# Reader_0001.net
KiCad netlist of a schematic drawn in EAGLE
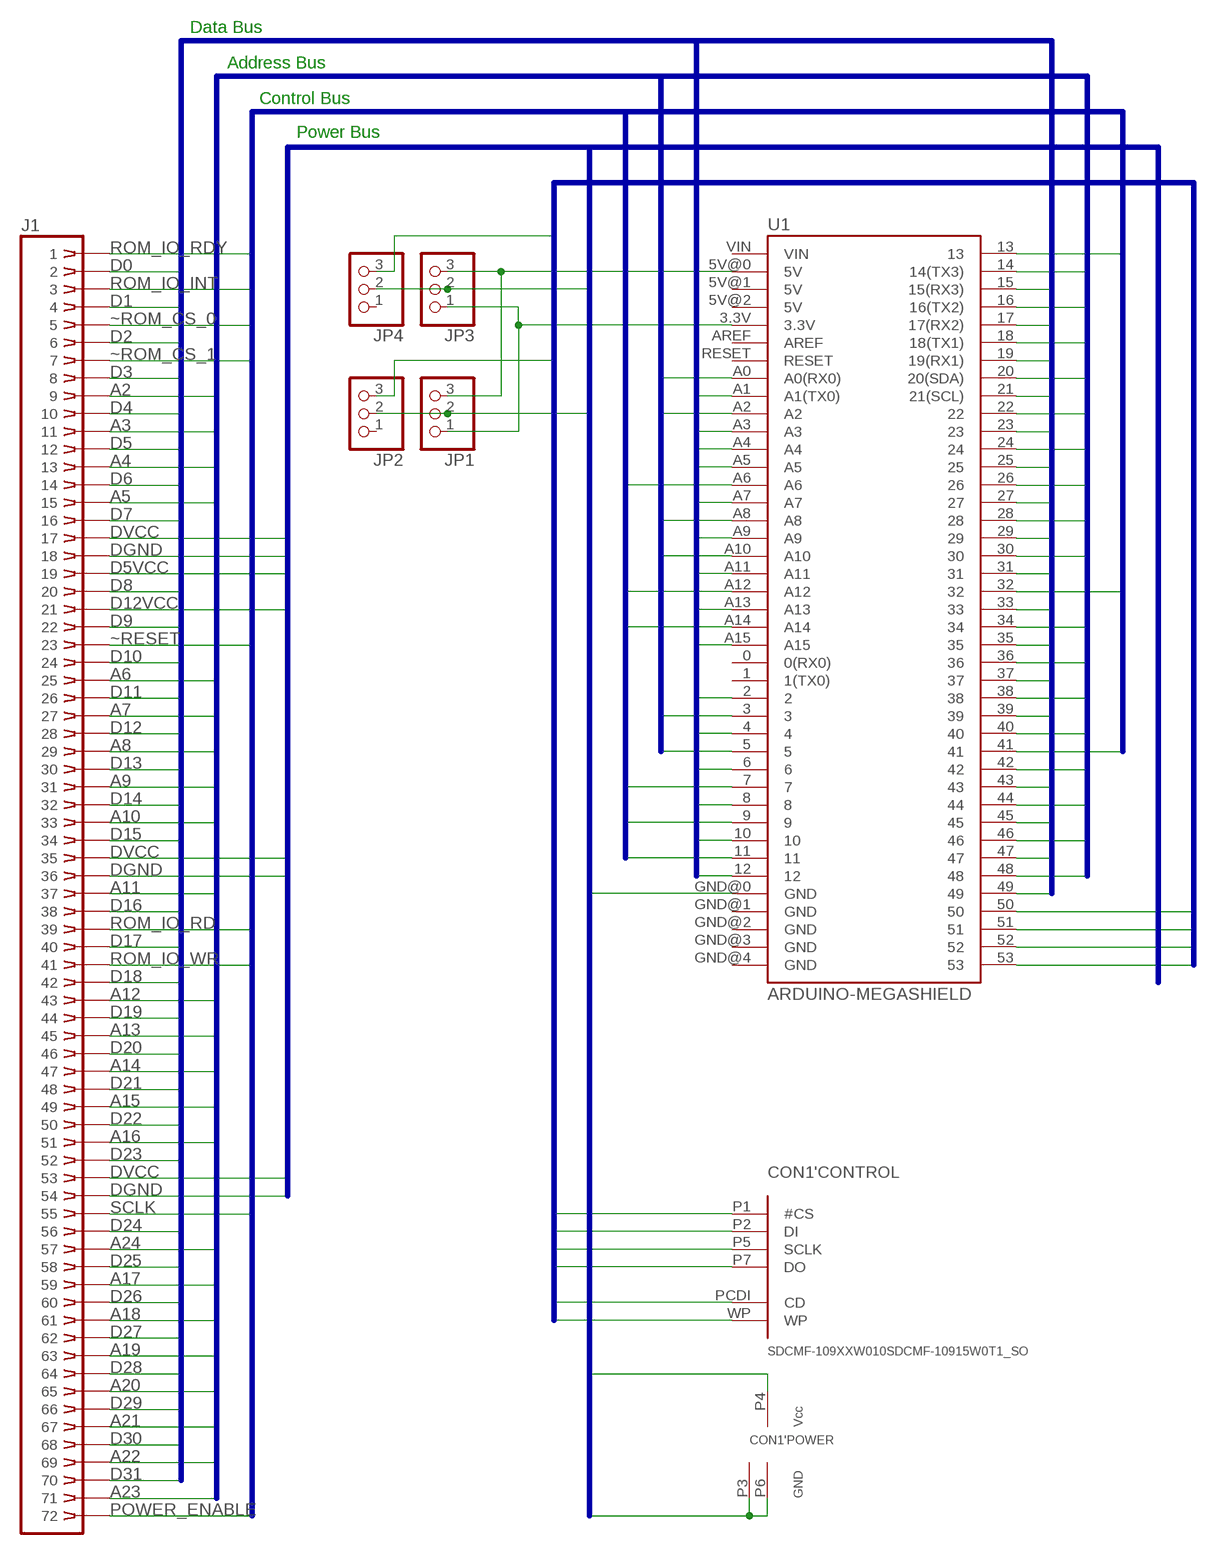
[diagram p0: schematic, sheet 1]

(export (version "E")
  (design (tool "Eeschema 10.0.6"))
  (components
    (comp (ref "CON1")
      (value "SDCMF-109XXW010SDCMF-10915W0T1_SO")
      (footprint "eagle-import:SDCMF-10915W0T1")
      (libsource (lib "eagle-import") (part "SDCMF-109XXW010SDCMF-10915W0T1_SO"))
    )
    (comp (ref "J1")
      (value "DIMM-M3")
      (footprint "eagle-import:177827-1")
      (libsource (lib "eagle-import") (part "DIMM-M3"))
    )
    (comp (ref "JP1")
      (value "PINHD-1X3")
      (footprint "eagle-import:1X03")
      (libsource (lib "eagle-import") (part "PINHD-1X3"))
    )
    (comp (ref "JP2")
      (value "PINHD-1X3")
      (footprint "eagle-import:1X03")
      (libsource (lib "eagle-import") (part "PINHD-1X3"))
    )
    (comp (ref "JP3")
      (value "PINHD-1X3")
      (footprint "eagle-import:1X03")
      (libsource (lib "eagle-import") (part "PINHD-1X3"))
    )
    (comp (ref "JP4")
      (value "PINHD-1X3")
      (footprint "eagle-import:1X03")
      (libsource (lib "eagle-import") (part "PINHD-1X3"))
    )
    (comp (ref "U1")
      (value "ARDUINO-MEGASHIELD")
      (footprint "eagle-import:ARDUINO_MEGA_SHIELD")
      (libsource (lib "eagle-import") (part "ARDUINO-MEGASHIELD"))
    )
  )
  (nets
    (net (code "1") (name "/A2") (class "Default")
      (node (ref "J1") (pin "9") (pinfunction "9_9") (pintype "passive"))
      (node (ref "U1") (pin "5") (pinfunction "5_5") (pintype "bidirectional"))
    )
    (net (code "2") (name "/A3") (class "Default")
      (node (ref "J1") (pin "11") (pinfunction "11_11") (pintype "passive"))
      (node (ref "U1") (pin "3") (pinfunction "3_3") (pintype "bidirectional"))
    )
    (net (code "3") (name "/A4") (class "Default")
      (node (ref "J1") (pin "13") (pinfunction "13_13") (pintype "passive"))
      (node (ref "U1") (pin "A0") (pinfunction "A0(RX0)_A0") (pintype "bidirectional"))
    )
    (net (code "4") (name "/A5") (class "Default")
      (node (ref "J1") (pin "15") (pinfunction "15_15") (pintype "passive"))
      (node (ref "U1") (pin "A2") (pinfunction "A2_A2") (pintype "bidirectional"))
    )
    (net (code "5") (name "/A6") (class "Default")
      (node (ref "J1") (pin "25") (pinfunction "25_25") (pintype "passive"))
      (node (ref "U1") (pin "14") (pinfunction "14(TX3)_14") (pintype "bidirectional"))
    )
    (net (code "6") (name "/A7") (class "Default")
      (node (ref "J1") (pin "27") (pinfunction "27_27") (pintype "passive"))
      (node (ref "U1") (pin "16") (pinfunction "16(TX2)_16") (pintype "bidirectional"))
    )
    (net (code "7") (name "/A8") (class "Default")
      (node (ref "J1") (pin "29") (pinfunction "29_29") (pintype "passive"))
      (node (ref "U1") (pin "18") (pinfunction "18(TX1)_18") (pintype "bidirectional"))
    )
    (net (code "8") (name "/A9") (class "Default")
      (node (ref "J1") (pin "31") (pinfunction "31_31") (pintype "passive"))
      (node (ref "U1") (pin "20") (pinfunction "20(SDA)_20") (pintype "bidirectional"))
    )
    (net (code "9") (name "/A10") (class "Default")
      (node (ref "J1") (pin "33") (pinfunction "33_33") (pintype "passive"))
      (node (ref "U1") (pin "A8") (pinfunction "A8_A8") (pintype "bidirectional"))
    )
    (net (code "10") (name "/A11") (class "Default")
      (node (ref "J1") (pin "37") (pinfunction "37_37") (pintype "passive"))
      (node (ref "U1") (pin "A10") (pinfunction "A10_A10") (pintype "bidirectional"))
    )
    (net (code "11") (name "/A12") (class "Default")
      (node (ref "J1") (pin "43") (pinfunction "43_43") (pintype "passive"))
      (node (ref "U1") (pin "22") (pinfunction "22_22") (pintype "bidirectional"))
    )
    (net (code "12") (name "/A13") (class "Default")
      (node (ref "J1") (pin "45") (pinfunction "45_45") (pintype "passive"))
      (node (ref "U1") (pin "24") (pinfunction "24_24") (pintype "bidirectional"))
    )
    (net (code "13") (name "/A14") (class "Default")
      (node (ref "J1") (pin "47") (pinfunction "47_47") (pintype "passive"))
      (node (ref "U1") (pin "26") (pinfunction "26_26") (pintype "bidirectional"))
    )
    (net (code "14") (name "/A15") (class "Default")
      (node (ref "J1") (pin "49") (pinfunction "49_49") (pintype "passive"))
      (node (ref "U1") (pin "28") (pinfunction "28_28") (pintype "bidirectional"))
    )
    (net (code "15") (name "/A16") (class "Default")
      (node (ref "J1") (pin "51") (pinfunction "51_51") (pintype "passive"))
      (node (ref "U1") (pin "30") (pinfunction "30_30") (pintype "bidirectional"))
    )
    (net (code "16") (name "/A17") (class "Default")
      (node (ref "J1") (pin "59") (pinfunction "59_59") (pintype "passive"))
      (node (ref "U1") (pin "36") (pinfunction "36_36") (pintype "bidirectional"))
    )
    (net (code "17") (name "/A18") (class "Default")
      (node (ref "J1") (pin "61") (pinfunction "61_61") (pintype "passive"))
      (node (ref "U1") (pin "38") (pinfunction "38_38") (pintype "bidirectional"))
    )
    (net (code "18") (name "/A19") (class "Default")
      (node (ref "J1") (pin "63") (pinfunction "63_63") (pintype "passive"))
      (node (ref "U1") (pin "40") (pinfunction "40_40") (pintype "bidirectional"))
    )
    (net (code "19") (name "/A20") (class "Default")
      (node (ref "J1") (pin "65") (pinfunction "65_65") (pintype "passive"))
      (node (ref "U1") (pin "48") (pinfunction "48_48") (pintype "bidirectional"))
    )
    (net (code "20") (name "/A21") (class "Default")
      (node (ref "J1") (pin "67") (pinfunction "67_67") (pintype "passive"))
      (node (ref "U1") (pin "46") (pinfunction "46_46") (pintype "bidirectional"))
    )
    (net (code "21") (name "/A22") (class "Default")
      (node (ref "J1") (pin "69") (pinfunction "69_69") (pintype "passive"))
      (node (ref "U1") (pin "44") (pinfunction "44_44") (pintype "bidirectional"))
    )
    (net (code "22") (name "/A23") (class "Default")
      (node (ref "J1") (pin "71") (pinfunction "71_71") (pintype "passive"))
      (node (ref "U1") (pin "42") (pinfunction "42_42") (pintype "bidirectional"))
    )
    (net (code "23") (name "/A24") (class "Default")
      (node (ref "J1") (pin "57") (pinfunction "57_57") (pintype "passive"))
      (node (ref "U1") (pin "34") (pinfunction "34_34") (pintype "bidirectional"))
    )
    (net (code "24") (name "/D0") (class "Default")
      (node (ref "J1") (pin "2") (pinfunction "2_2") (pintype "passive"))
      (node (ref "U1") (pin "12") (pinfunction "12_12") (pintype "bidirectional"))
    )
    (net (code "25") (name "/D1") (class "Default")
      (node (ref "J1") (pin "4") (pinfunction "4_4") (pintype "passive"))
      (node (ref "U1") (pin "10") (pinfunction "10_10") (pintype "bidirectional"))
    )
    (net (code "26") (name "/D2") (class "Default")
      (node (ref "J1") (pin "6") (pinfunction "6_6") (pintype "passive"))
      (node (ref "U1") (pin "8") (pinfunction "8_8") (pintype "bidirectional"))
    )
    (net (code "27") (name "/D3") (class "Default")
      (node (ref "J1") (pin "8") (pinfunction "8_8") (pintype "passive"))
      (node (ref "U1") (pin "6") (pinfunction "6_6") (pintype "bidirectional"))
    )
    (net (code "28") (name "/D4") (class "Default")
      (node (ref "J1") (pin "10") (pinfunction "10_10") (pintype "passive"))
      (node (ref "U1") (pin "4") (pinfunction "4_4") (pintype "bidirectional"))
    )
    (net (code "29") (name "/D5") (class "Default")
      (node (ref "J1") (pin "12") (pinfunction "12_12") (pintype "passive"))
      (node (ref "U1") (pin "2") (pinfunction "2_2") (pintype "bidirectional"))
    )
    (net (code "30") (name "/D5VCC") (class "Default")
      (node (ref "J1") (pin "19") (pinfunction "19_19") (pintype "passive"))
      (node (ref "JP1") (pin "2") (pinfunction "2_2") (pintype "passive"))
      (node (ref "JP2") (pin "2") (pinfunction "2_2") (pintype "passive"))
    )
    (net (code "31") (name "/D6") (class "Default")
      (node (ref "J1") (pin "14") (pinfunction "14_14") (pintype "passive"))
      (node (ref "U1") (pin "A1") (pinfunction "A1(TX0)_A1") (pintype "bidirectional"))
    )
    (net (code "32") (name "/D7") (class "Default")
      (node (ref "J1") (pin "16") (pinfunction "16_16") (pintype "passive"))
      (node (ref "U1") (pin "A3") (pinfunction "A3_A3") (pintype "bidirectional"))
    )
    (net (code "33") (name "/D8") (class "Default")
      (node (ref "J1") (pin "20") (pinfunction "20_20") (pintype "passive"))
      (node (ref "U1") (pin "A4") (pinfunction "A4_A4") (pintype "bidirectional"))
    )
    (net (code "34") (name "/D9") (class "Default")
      (node (ref "J1") (pin "22") (pinfunction "22_22") (pintype "passive"))
      (node (ref "U1") (pin "A5") (pinfunction "A5_A5") (pintype "bidirectional"))
    )
    (net (code "35") (name "/D10") (class "Default")
      (node (ref "J1") (pin "24") (pinfunction "24_24") (pintype "passive"))
      (node (ref "U1") (pin "A7") (pinfunction "A7_A7") (pintype "bidirectional"))
    )
    (net (code "36") (name "/D11") (class "Default")
      (node (ref "J1") (pin "26") (pinfunction "26_26") (pintype "passive"))
      (node (ref "U1") (pin "15") (pinfunction "15(RX3)_15") (pintype "bidirectional"))
    )
    (net (code "37") (name "/D12") (class "Default")
      (node (ref "J1") (pin "28") (pinfunction "28_28") (pintype "passive"))
      (node (ref "U1") (pin "17") (pinfunction "17(RX2)_17") (pintype "bidirectional"))
    )
    (net (code "38") (name "/D12VCC") (class "Default")
      (node (ref "J1") (pin "21") (pinfunction "21_21") (pintype "passive"))
    )
    (net (code "39") (name "/D13") (class "Default")
      (node (ref "J1") (pin "30") (pinfunction "30_30") (pintype "passive"))
      (node (ref "U1") (pin "19") (pinfunction "19(RX1)_19") (pintype "bidirectional"))
    )
    (net (code "40") (name "/D14") (class "Default")
      (node (ref "J1") (pin "32") (pinfunction "32_32") (pintype "passive"))
      (node (ref "U1") (pin "21") (pinfunction "21(SCL)_21") (pintype "bidirectional"))
    )
    (net (code "41") (name "/D15") (class "Default")
      (node (ref "J1") (pin "34") (pinfunction "34_34") (pintype "passive"))
      (node (ref "U1") (pin "A9") (pinfunction "A9_A9") (pintype "bidirectional"))
    )
    (net (code "42") (name "/D16") (class "Default")
      (node (ref "J1") (pin "38") (pinfunction "38_38") (pintype "passive"))
      (node (ref "U1") (pin "A11") (pinfunction "A11_A11") (pintype "bidirectional"))
    )
    (net (code "43") (name "/D17") (class "Default")
      (node (ref "J1") (pin "40") (pinfunction "40_40") (pintype "passive"))
      (node (ref "U1") (pin "A13") (pinfunction "A13_A13") (pintype "bidirectional"))
    )
    (net (code "44") (name "/D18") (class "Default")
      (node (ref "J1") (pin "42") (pinfunction "42_42") (pintype "passive"))
      (node (ref "U1") (pin "A15") (pinfunction "A15_A15") (pintype "bidirectional"))
    )
    (net (code "45") (name "/D19") (class "Default")
      (node (ref "J1") (pin "44") (pinfunction "44_44") (pintype "passive"))
      (node (ref "U1") (pin "23") (pinfunction "23_23") (pintype "bidirectional"))
    )
    (net (code "46") (name "/D20") (class "Default")
      (node (ref "J1") (pin "46") (pinfunction "46_46") (pintype "passive"))
      (node (ref "U1") (pin "25") (pinfunction "25_25") (pintype "bidirectional"))
    )
    (net (code "47") (name "/D21") (class "Default")
      (node (ref "J1") (pin "48") (pinfunction "48_48") (pintype "passive"))
      (node (ref "U1") (pin "27") (pinfunction "27_27") (pintype "bidirectional"))
    )
    (net (code "48") (name "/D22") (class "Default")
      (node (ref "J1") (pin "50") (pinfunction "50_50") (pintype "passive"))
      (node (ref "U1") (pin "29") (pinfunction "29_29") (pintype "bidirectional"))
    )
    (net (code "49") (name "/D23") (class "Default")
      (node (ref "J1") (pin "52") (pinfunction "52_52") (pintype "passive"))
      (node (ref "U1") (pin "31") (pinfunction "31_31") (pintype "bidirectional"))
    )
    (net (code "50") (name "/D24") (class "Default")
      (node (ref "J1") (pin "56") (pinfunction "56_56") (pintype "passive"))
      (node (ref "U1") (pin "33") (pinfunction "33_33") (pintype "bidirectional"))
    )
    (net (code "51") (name "/D25") (class "Default")
      (node (ref "J1") (pin "58") (pinfunction "58_58") (pintype "passive"))
      (node (ref "U1") (pin "35") (pinfunction "35_35") (pintype "bidirectional"))
    )
    (net (code "52") (name "/D26") (class "Default")
      (node (ref "J1") (pin "60") (pinfunction "60_60") (pintype "passive"))
      (node (ref "U1") (pin "37") (pinfunction "37_37") (pintype "bidirectional"))
    )
    (net (code "53") (name "/D27") (class "Default")
      (node (ref "J1") (pin "62") (pinfunction "62_62") (pintype "passive"))
      (node (ref "U1") (pin "39") (pinfunction "39_39") (pintype "bidirectional"))
    )
    (net (code "54") (name "/D28") (class "Default")
      (node (ref "J1") (pin "64") (pinfunction "64_64") (pintype "passive"))
      (node (ref "U1") (pin "49") (pinfunction "49_49") (pintype "bidirectional"))
    )
    (net (code "55") (name "/D29") (class "Default")
      (node (ref "J1") (pin "66") (pinfunction "66_66") (pintype "passive"))
      (node (ref "U1") (pin "47") (pinfunction "47_47") (pintype "bidirectional"))
    )
    (net (code "56") (name "/D30") (class "Default")
      (node (ref "J1") (pin "68") (pinfunction "68_68") (pintype "passive"))
      (node (ref "U1") (pin "45") (pinfunction "45_45") (pintype "bidirectional"))
    )
    (net (code "57") (name "/D31") (class "Default")
      (node (ref "J1") (pin "70") (pinfunction "70_70") (pintype "passive"))
      (node (ref "U1") (pin "43") (pinfunction "43_43") (pintype "bidirectional"))
    )
    (net (code "58") (name "/DGND") (class "Default")
      (node (ref "CON1") (pin "P3") (pinfunction "GND_P3") (pintype "power_in"))
      (node (ref "CON1") (pin "P6") (pinfunction "GND_P6") (pintype "power_in"))
      (node (ref "J1") (pin "18") (pinfunction "18_18") (pintype "passive"))
      (node (ref "J1") (pin "36") (pinfunction "36_36") (pintype "passive"))
      (node (ref "J1") (pin "54") (pinfunction "54_54") (pintype "passive"))
      (node (ref "U1") (pin "GND@0") (pinfunction "GND_GND@0") (pintype "bidirectional"))
    )
    (net (code "59") (name "/DVCC") (class "Default")
      (node (ref "CON1") (pin "P4") (pinfunction "VCC_P4") (pintype "power_in"))
      (node (ref "J1") (pin "17") (pinfunction "17_17") (pintype "passive"))
      (node (ref "J1") (pin "35") (pinfunction "35_35") (pintype "passive"))
      (node (ref "J1") (pin "53") (pinfunction "53_53") (pintype "passive"))
      (node (ref "JP3") (pin "2") (pinfunction "2_2") (pintype "passive"))
      (node (ref "JP4") (pin "2") (pinfunction "2_2") (pintype "passive"))
    )
    (net (code "60") (name "/POWER_ENABLE") (class "Default")
      (node (ref "J1") (pin "72") (pinfunction "72_72") (pintype "passive"))
      (node (ref "U1") (pin "41") (pinfunction "41_41") (pintype "bidirectional"))
    )
    (net (code "61") (name "/ROM_IO_INT") (class "Default")
      (node (ref "J1") (pin "3") (pinfunction "3_3") (pintype "passive"))
      (node (ref "U1") (pin "11") (pinfunction "11_11") (pintype "bidirectional"))
    )
    (net (code "62") (name "/ROM_IO_RD") (class "Default")
      (node (ref "J1") (pin "39") (pinfunction "39_39") (pintype "passive"))
      (node (ref "U1") (pin "A12") (pinfunction "A12_A12") (pintype "bidirectional"))
    )
    (net (code "63") (name "/ROM_IO_RDY") (class "Default")
      (node (ref "J1") (pin "1") (pinfunction "1_1") (pintype "passive"))
      (node (ref "U1") (pin "13") (pinfunction "13_13") (pintype "bidirectional"))
    )
    (net (code "64") (name "/ROM_IO_WR") (class "Default")
      (node (ref "J1") (pin "41") (pinfunction "41_41") (pintype "passive"))
      (node (ref "U1") (pin "A14") (pinfunction "A14_A14") (pintype "bidirectional"))
    )
    (net (code "65") (name "/SCLK") (class "Default")
      (node (ref "J1") (pin "55") (pinfunction "55_55") (pintype "passive"))
      (node (ref "U1") (pin "32") (pinfunction "32_32") (pintype "bidirectional"))
    )
    (net (code "66") (name "/SD_CLCK") (class "Default")
      (node (ref "CON1") (pin "P5") (pinfunction "SCLK_P5") (pintype "input"))
      (node (ref "U1") (pin "52") (pinfunction "52_52") (pintype "bidirectional"))
    )
    (net (code "67") (name "/SD_CS") (class "Default")
      (node (ref "CON1") (pin "P1") (pinfunction "#CS_P1") (pintype "input"))
      (node (ref "U1") (pin "53") (pinfunction "53_53") (pintype "bidirectional"))
    )
    (net (code "68") (name "/SD_DI") (class "Default")
      (node (ref "CON1") (pin "P2") (pinfunction "DI_P2") (pintype "input"))
      (node (ref "JP2") (pin "3") (pinfunction "3_3") (pintype "passive"))
      (node (ref "U1") (pin "51") (pinfunction "51_51") (pintype "bidirectional"))
    )
    (net (code "69") (name "/SD_DO") (class "Default")
      (node (ref "CON1") (pin "P7") (pinfunction "DO_P7") (pintype "output"))
      (node (ref "JP4") (pin "3") (pinfunction "3_3") (pintype "passive"))
      (node (ref "U1") (pin "50") (pinfunction "50_50") (pintype "bidirectional"))
    )
    (net (code "70") (name "/~{RESET}") (class "Default")
      (node (ref "J1") (pin "23") (pinfunction "23_23") (pintype "passive"))
      (node (ref "U1") (pin "A6") (pinfunction "A6_A6") (pintype "bidirectional"))
    )
    (net (code "71") (name "/~{ROM_CS_0}") (class "Default")
      (node (ref "J1") (pin "5") (pinfunction "5_5") (pintype "passive"))
      (node (ref "U1") (pin "9") (pinfunction "9_9") (pintype "bidirectional"))
    )
    (net (code "72") (name "/~{ROM_CS_1}") (class "Default")
      (node (ref "J1") (pin "7") (pinfunction "7_7") (pintype "passive"))
      (node (ref "U1") (pin "7") (pinfunction "7_7") (pintype "bidirectional"))
    )
    (net (code "73") (name "Net-(JP1-Pad1)") (class "Default")
      (node (ref "JP1") (pin "1") (pinfunction "1_1") (pintype "passive"))
      (node (ref "JP3") (pin "1") (pinfunction "1_1") (pintype "passive"))
      (node (ref "U1") (pin "3.3V") (pinfunction "3.3V_3.3V") (pintype "bidirectional"))
    )
    (net (code "74") (name "Net-(JP1-Pad3)") (class "Default")
      (node (ref "JP1") (pin "3") (pinfunction "3_3") (pintype "passive"))
      (node (ref "JP3") (pin "3") (pinfunction "3_3") (pintype "passive"))
      (node (ref "U1") (pin "5V@0") (pinfunction "5V_5V@0") (pintype "bidirectional"))
    )
    (net (code "75") (name "unconnected-(CON1-PadWP)") (class "Default")
      (node (ref "CON1") (pin "WP") (pinfunction "WP_WP") (pintype "open_collector"))
    )
    (net (code "76") (name "unconnected-(CON1A-CD-PadPCDI)") (class "Default")
      (node (ref "CON1") (pin "PCDI") (pinfunction "CD_PCDI") (pintype "open_collector"))
    )
    (net (code "77") (name "unconnected-(JP2-Pad1)") (class "Default")
      (node (ref "JP2") (pin "1") (pinfunction "1_1") (pintype "passive"))
    )
    (net (code "78") (name "unconnected-(JP4-Pad1)") (class "Default")
      (node (ref "JP4") (pin "1") (pinfunction "1_1") (pintype "passive"))
    )
    (net (code "79") (name "unconnected-(U1-0(RX0)-Pad0)") (class "Default")
      (node (ref "U1") (pin "0") (pinfunction "0(RX0)_0") (pintype "bidirectional"))
    )
    (net (code "80") (name "unconnected-(U1-1(TX0)-Pad1)") (class "Default")
      (node (ref "U1") (pin "1") (pinfunction "1(TX0)_1") (pintype "bidirectional"))
    )
    (net (code "81") (name "unconnected-(U1-5V-Pad5V@1)") (class "Default")
      (node (ref "U1") (pin "5V@1") (pinfunction "5V_5V@1") (pintype "bidirectional"))
    )
    (net (code "82") (name "unconnected-(U1-5V-Pad5V@2)") (class "Default")
      (node (ref "U1") (pin "5V@2") (pinfunction "5V_5V@2") (pintype "bidirectional"))
    )
    (net (code "83") (name "unconnected-(U1-GND-PadGND@1)") (class "Default")
      (node (ref "U1") (pin "GND@1") (pinfunction "GND_GND@1") (pintype "bidirectional"))
    )
    (net (code "84") (name "unconnected-(U1-GND-PadGND@2)") (class "Default")
      (node (ref "U1") (pin "GND@2") (pinfunction "GND_GND@2") (pintype "bidirectional"))
    )
    (net (code "85") (name "unconnected-(U1-GND-PadGND@3)") (class "Default")
      (node (ref "U1") (pin "GND@3") (pinfunction "GND_GND@3") (pintype "bidirectional"))
    )
    (net (code "86") (name "unconnected-(U1-GND-PadGND@4)") (class "Default")
      (node (ref "U1") (pin "GND@4") (pinfunction "GND_GND@4") (pintype "bidirectional"))
    )
    (net (code "87") (name "unconnected-(U1-PadAREF)") (class "Default")
      (node (ref "U1") (pin "AREF") (pinfunction "AREF_AREF") (pintype "bidirectional"))
    )
    (net (code "88") (name "unconnected-(U1-PadRESET)") (class "Default")
      (node (ref "U1") (pin "RESET") (pinfunction "RESET_RESET") (pintype "bidirectional"))
    )
    (net (code "89") (name "unconnected-(U1-PadVIN)") (class "Default")
      (node (ref "U1") (pin "VIN") (pinfunction "VIN_VIN") (pintype "bidirectional"))
    )
  )
)
